# linear.net
KiCad netlist of a schematic drawn in Altium Designer
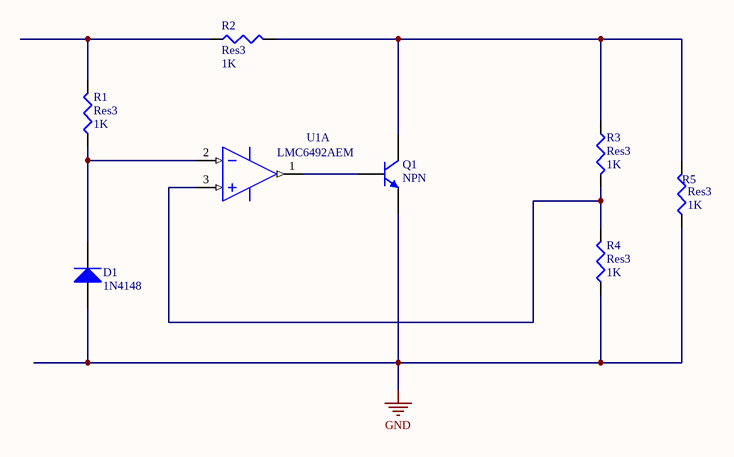
[diagram p0: linear.SchDoc]

(export (version "E")
  (design (tool "Eeschema 10.0.6"))
  (components
    (comp (ref "D1")
      (value "1N4148")
      (footprint "NXP-SOD27-2_V")
      (description "High-speed Diode, 100 V, 450 mA, 2-Pin SOD27, RoHS")
      (fields (field (name "MANUFACTURER") "NXP Semiconductors"))
      (libsource (lib "Altium Content Vault") (part "NXP-A1K2-2"))
    )
    (comp (ref "Q1")
      (value "NPN")
      (footprint "TO-226-AA")
      (description "NPN Bipolar Transistor")
      (fields (field (name "PUBLISHER") "Altium Limited"))
      (libsource (lib "Miscellaneous Devices") (part "NPN"))
    )
    (comp (ref "R1")
      (value "Res3")
      (footprint "J1-0603")
      (description "Resistor")
      (fields (field (name "ALTIUM_VALUE") "1K") (field (name "PUBLISHER") "Altium Limited"))
      (libsource (lib "Miscellaneous Devices") (part "Res3"))
    )
    (comp (ref "R2")
      (value "Res3")
      (footprint "J1-0603")
      (description "Resistor")
      (fields (field (name "ALTIUM_VALUE") "1K") (field (name "PUBLISHER") "Altium Limited"))
      (libsource (lib "Miscellaneous Devices") (part "Res3"))
    )
    (comp (ref "R3")
      (value "Res3")
      (footprint "J1-0603")
      (description "Resistor")
      (fields (field (name "ALTIUM_VALUE") "1K") (field (name "PUBLISHER") "Altium Limited"))
      (libsource (lib "Miscellaneous Devices") (part "Res3"))
    )
    (comp (ref "R4")
      (value "Res3")
      (footprint "J1-0603")
      (description "Resistor")
      (fields (field (name "ALTIUM_VALUE") "1K") (field (name "PUBLISHER") "Altium Limited"))
      (libsource (lib "Miscellaneous Devices") (part "Res3"))
    )
    (comp (ref "R5")
      (value "Res3")
      (footprint "J1-0603")
      (description "Resistor")
      (fields (field (name "ALTIUM_VALUE") "1K") (field (name "PUBLISHER") "Altium Limited"))
      (libsource (lib "Miscellaneous Devices") (part "Res3"))
    )
    (comp (ref "U1")
      (value "LMC6492AEM")
      (footprint "D0008A_L")
      (description "Dual CMOS Rail-to-Rail Input and Output Operational Amplifier, 8-pin Narrow SOIC")
      (fields (field (name "MANUFACTURER") "Texas Instruments"))
      (libsource (lib "Altium Content Vault") (part "AMP-OPA-LM6132-8"))
    )
  )
  (nets
    (net (code "1") (name "GND") (class "Default")
      (node (ref "D1") (pin "1") (pinfunction "A_1") (pintype "passive"))
      (node (ref "Q1") (pin "3") (pinfunction "E_3") (pintype "passive"))
      (node (ref "R4") (pin "1") (pinfunction "1_1") (pintype "passive"))
      (node (ref "R5") (pin "1") (pinfunction "1_1") (pintype "passive"))
    )
    (net (code "2") (name "Net-(D1-K)") (class "Default")
      (node (ref "D1") (pin "2") (pinfunction "K_2") (pintype "passive"))
      (node (ref "R1") (pin "1") (pinfunction "1_1") (pintype "passive"))
      (node (ref "U1") (pin "2") (pinfunction "INA-_2") (pintype "input"))
    )
    (net (code "3") (name "Net-(Q1-B)") (class "Default")
      (node (ref "Q1") (pin "2") (pinfunction "B_2") (pintype "passive"))
      (node (ref "U1") (pin "1") (pinfunction "OUTA_1") (pintype "output"))
    )
    (net (code "4") (name "Net-(Q1-C)") (class "Default")
      (node (ref "Q1") (pin "1") (pinfunction "C_1") (pintype "passive"))
      (node (ref "R2") (pin "2") (pinfunction "2_2") (pintype "passive"))
      (node (ref "R3") (pin "1") (pinfunction "1_1") (pintype "passive"))
      (node (ref "R5") (pin "2") (pinfunction "2_2") (pintype "passive"))
    )
    (net (code "5") (name "Net-(R1-Pad2)") (class "Default")
      (node (ref "R1") (pin "2") (pinfunction "2_2") (pintype "passive"))
      (node (ref "R2") (pin "1") (pinfunction "1_1") (pintype "passive"))
    )
    (net (code "6") (name "Net-(U1A-INA+)") (class "Default")
      (node (ref "R3") (pin "2") (pinfunction "2_2") (pintype "passive"))
      (node (ref "R4") (pin "2") (pinfunction "2_2") (pintype "passive"))
      (node (ref "U1") (pin "3") (pinfunction "INA+_3") (pintype "input"))
    )
  )
)
